# HB-UNI-Sen-RFID-RC_V1_0.net
KiCad netlist of a schematic drawn in EAGLE
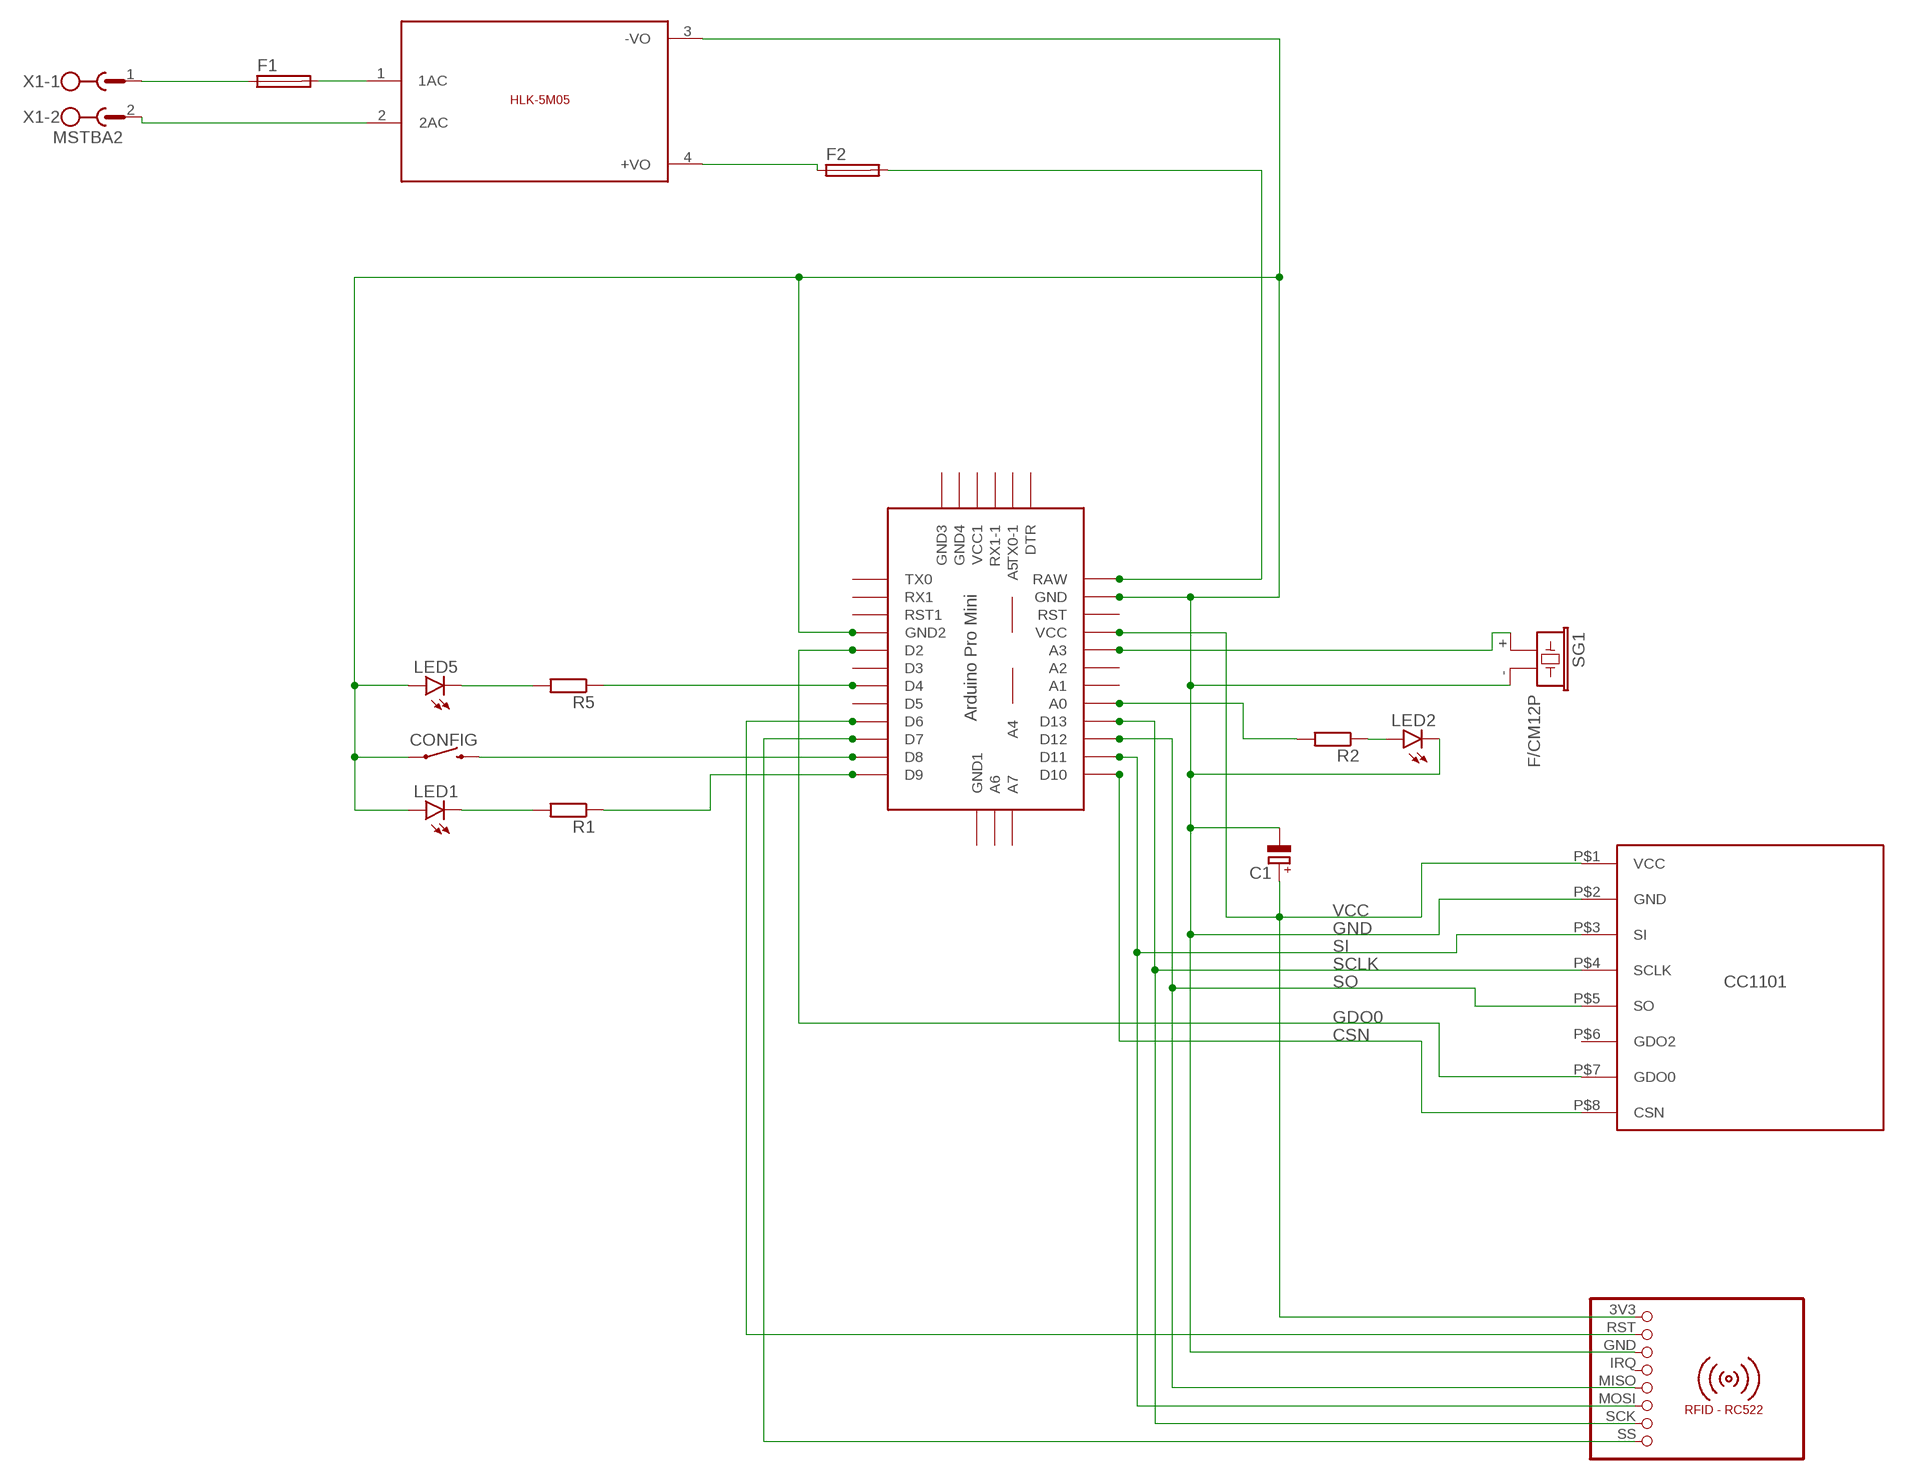
[diagram p0: schematic, sheet 1]

(export (version "E")
  (design (tool "Eeschema 10.0.6"))
  (components
    (comp (ref "C1")
      (value "CPOL-EUE2.5-5")
      (footprint "eagle-import:E2,5-5")
      (libsource (lib "eagle-import") (part "CPOL-EUE2.5-5"))
    )
    (comp (ref "CONFIG")
      (value "MOMENTARY-SWITCH-SPST-PTH-6.0MM-KIT")
      (footprint "eagle-import:TACTILE_SWITCH_PTH_6.0MM_KIT")
      (libsource (lib "eagle-import") (part "MOMENTARY-SWITCH-SPST-PTH-6.0MM-KIT"))
    )
    (comp (ref "F1")
      (value "SH22,5A")
      (footprint "eagle-import:SH22,5A")
      (fields (field (name "MPN") "0031.7701.11"))
      (libsource (lib "eagle-import") (part "SH22,5A"))
    )
    (comp (ref "F2")
      (value "SH22,5A")
      (footprint "eagle-import:SH22,5A")
      (fields (field (name "MPN") "0031.7701.11"))
      (libsource (lib "eagle-import") (part "SH22,5A"))
    )
    (comp (ref "LED1")
      (value "LED3MM")
      (footprint "eagle-import:LED3MM")
      (libsource (lib "eagle-import") (part "LED3MM"))
    )
    (comp (ref "LED2")
      (value "LED3MM")
      (footprint "eagle-import:LED3MM")
      (libsource (lib "eagle-import") (part "LED3MM"))
    )
    (comp (ref "LED5")
      (value "LED3MM")
      (footprint "eagle-import:LED3MM")
      (libsource (lib "eagle-import") (part "LED3MM"))
    )
    (comp (ref "M1")
      (value "RFID-RC522")
      (footprint "eagle-import:RFID-RC522")
      (libsource (lib "eagle-import") (part "RFID-RC522"))
    )
    (comp (ref "R1")
      (value "R-EU_0309/10")
      (footprint "eagle-import:0309_10")
      (libsource (lib "eagle-import") (part "R-EU_0309/10"))
    )
    (comp (ref "R2")
      (value "R-EU_0309/10")
      (footprint "eagle-import:0309_10")
      (libsource (lib "eagle-import") (part "R-EU_0309/10"))
    )
    (comp (ref "R5")
      (value "R-EU_0309/10")
      (footprint "eagle-import:0309_10")
      (libsource (lib "eagle-import") (part "R-EU_0309/10"))
    )
    (comp (ref "SG1")
      (value "F/CM12P")
      (footprint "eagle-import:F_CM12P")
      (libsource (lib "eagle-import") (part "F/CM12P"))
    )
    (comp (ref "U$1")
      (value "CC1101")
      (footprint "eagle-import:CC1101")
      (libsource (lib "eagle-import") (part "CC1101"))
    )
    (comp (ref "U$2")
      (value "ABK-PRO-MINI")
      (footprint "eagle-import:ABK-PRO-MINI")
      (libsource (lib "eagle-import") (part "ABK-PRO-MINI"))
    )
    (comp (ref "U$3")
      (value "5VDC/5W")
      (footprint "eagle-import:HLK-5M05")
      (libsource (lib "eagle-import") (part "HLK-5M05"))
    )
    (comp (ref "X1")
      (value "MSTBA2")
      (footprint "eagle-import:MSTBA2")
      (fields (field (name "MF") "FARNELL") (field (name "MPN") "1757242"))
      (libsource (lib "eagle-import") (part "MSTBA2"))
    )
  )
  (nets
    (net (code "1") (name "/CSN") (class "Default")
      (node (ref "U$1") (pin "P$8") (pinfunction "CSN_P$8") (pintype "bidirectional"))
      (node (ref "U$2") (pin "D10") (pinfunction "D10_D10") (pintype "bidirectional"))
    )
    (net (code "2") (name "/GDO0") (class "Default")
      (node (ref "U$1") (pin "P$7") (pinfunction "GDO0_P$7") (pintype "bidirectional"))
      (node (ref "U$2") (pin "D2") (pinfunction "D2_D2") (pintype "bidirectional"))
    )
    (net (code "3") (name "/GND") (class "Default")
      (node (ref "C1") (pin "-") (pinfunction "-_-") (pintype "passive"))
      (node (ref "CONFIG") (pin "1") (pinfunction "1_1") (pintype "passive"))
      (node (ref "LED1") (pin "A") (pinfunction "A_A") (pintype "passive"))
      (node (ref "LED2") (pin "K") (pinfunction "C_K") (pintype "passive"))
      (node (ref "LED5") (pin "A") (pinfunction "A_A") (pintype "passive"))
      (node (ref "M1") (pin "GND") (pinfunction "3_GND") (pintype "passive"))
      (node (ref "SG1") (pin "-") (pinfunction "2_-") (pintype "passive"))
      (node (ref "U$1") (pin "P$2") (pinfunction "GND_P$2") (pintype "bidirectional"))
      (node (ref "U$2") (pin "GND") (pinfunction "GND_GND") (pintype "bidirectional"))
      (node (ref "U$2") (pin "GND1") (pinfunction "GND2_GND1") (pintype "bidirectional"))
      (node (ref "U$3") (pin "3") (pinfunction "-VO_3") (pintype "bidirectional"))
    )
    (net (code "4") (name "/SCLK") (class "Default")
      (node (ref "M1") (pin "SCK") (pinfunction "7_SCK") (pintype "passive"))
      (node (ref "U$1") (pin "P$4") (pinfunction "SCLK_P$4") (pintype "bidirectional"))
      (node (ref "U$2") (pin "D13") (pinfunction "D13_D13") (pintype "bidirectional"))
    )
    (net (code "5") (name "/SI") (class "Default")
      (node (ref "M1") (pin "MOSI") (pinfunction "6_MOSI") (pintype "passive"))
      (node (ref "U$1") (pin "P$3") (pinfunction "SI_P$3") (pintype "bidirectional"))
      (node (ref "U$2") (pin "D11") (pinfunction "D11_D11") (pintype "bidirectional"))
    )
    (net (code "6") (name "/SO") (class "Default")
      (node (ref "M1") (pin "MISO") (pinfunction "5_MISO") (pintype "passive"))
      (node (ref "U$1") (pin "P$5") (pinfunction "SO_P$5") (pintype "bidirectional"))
      (node (ref "U$2") (pin "D12") (pinfunction "D12_D12") (pintype "bidirectional"))
    )
    (net (code "7") (name "/VCC") (class "Default")
      (node (ref "C1") (pin "+") (pinfunction "+_+") (pintype "passive"))
      (node (ref "M1") (pin "3V3") (pinfunction "1_3V3") (pintype "passive"))
      (node (ref "U$1") (pin "P$1") (pinfunction "VCC_P$1") (pintype "bidirectional"))
      (node (ref "U$2") (pin "VCC") (pinfunction "VCC_VCC") (pintype "bidirectional"))
    )
    (net (code "8") (name "Net-(CONFIG-2)") (class "Default")
      (node (ref "CONFIG") (pin "3") (pinfunction "2_3") (pintype "passive"))
      (node (ref "U$2") (pin "D8") (pinfunction "D8_D8") (pintype "bidirectional"))
    )
    (net (code "9") (name "Net-(F1-Pad1)") (class "Default")
      (node (ref "F1") (pin "1") (pinfunction "1_1") (pintype "passive"))
      (node (ref "X1") (pin "1") (pinfunction "1_1") (pintype "passive"))
    )
    (net (code "10") (name "Net-(F2-Pad2)") (class "Default")
      (node (ref "F2") (pin "2") (pinfunction "2_2") (pintype "passive"))
      (node (ref "U$2") (pin "RAW") (pinfunction "RAW_RAW") (pintype "bidirectional"))
    )
    (net (code "11") (name "Net-(LED1-C)") (class "Default")
      (node (ref "LED1") (pin "K") (pinfunction "C_K") (pintype "passive"))
      (node (ref "R1") (pin "2") (pinfunction "2_2") (pintype "passive"))
    )
    (net (code "12") (name "Net-(LED2-PadA)") (class "Default")
      (node (ref "LED2") (pin "A") (pinfunction "A_A") (pintype "passive"))
      (node (ref "R2") (pin "1") (pinfunction "1_1") (pintype "passive"))
    )
    (net (code "13") (name "Net-(LED5-C)") (class "Default")
      (node (ref "LED5") (pin "K") (pinfunction "C_K") (pintype "passive"))
      (node (ref "R5") (pin "2") (pinfunction "2_2") (pintype "passive"))
    )
    (net (code "14") (name "Net-(M1-2)") (class "Default")
      (node (ref "M1") (pin "RST") (pinfunction "2_RST") (pintype "passive"))
      (node (ref "U$2") (pin "D6") (pinfunction "D6_D6") (pintype "bidirectional"))
    )
    (net (code "15") (name "Net-(M1-8)") (class "Default")
      (node (ref "M1") (pin "SS") (pinfunction "8_SS") (pintype "passive"))
      (node (ref "U$2") (pin "D7") (pinfunction "D7_D7") (pintype "bidirectional"))
    )
    (net (code "16") (name "Net-(R1-Pad1)") (class "Default")
      (node (ref "R1") (pin "1") (pinfunction "1_1") (pintype "passive"))
      (node (ref "U$2") (pin "D9") (pinfunction "D9_D9") (pintype "bidirectional"))
    )
    (net (code "17") (name "Net-(R2-Pad2)") (class "Default")
      (node (ref "R2") (pin "2") (pinfunction "2_2") (pintype "passive"))
      (node (ref "U$2") (pin "A0") (pinfunction "A0_A0") (pintype "bidirectional"))
    )
    (net (code "18") (name "Net-(R5-Pad1)") (class "Default")
      (node (ref "R5") (pin "1") (pinfunction "1_1") (pintype "passive"))
      (node (ref "U$2") (pin "D4") (pinfunction "D4_D4") (pintype "bidirectional"))
    )
    (net (code "19") (name "Net-(SG1-1)") (class "Default")
      (node (ref "SG1") (pin "+") (pinfunction "1_+") (pintype "passive"))
      (node (ref "U$2") (pin "A3") (pinfunction "A3_A3") (pintype "bidirectional"))
    )
    (net (code "20") (name "Net-(U$3-+VO)") (class "Default")
      (node (ref "F2") (pin "1") (pinfunction "1_1") (pintype "passive"))
      (node (ref "U$3") (pin "4") (pinfunction "+VO_4") (pintype "bidirectional"))
    )
    (net (code "21") (name "Net-(U$3-1AC)") (class "Default")
      (node (ref "F1") (pin "2") (pinfunction "2_2") (pintype "passive"))
      (node (ref "U$3") (pin "1") (pinfunction "1AC_1") (pintype "bidirectional"))
    )
    (net (code "22") (name "Net-(U$3-2AC)") (class "Default")
      (node (ref "U$3") (pin "2") (pinfunction "2AC_2") (pintype "bidirectional"))
      (node (ref "X1") (pin "2") (pinfunction "1_2") (pintype "passive"))
    )
    (net (code "23") (name "unconnected-(M1-4-PadIRQ)") (class "Default")
      (node (ref "M1") (pin "IRQ") (pinfunction "4_IRQ") (pintype "passive"))
    )
    (net (code "24") (name "unconnected-(U$1-GDO2-PadP$6)") (class "Default")
      (node (ref "U$1") (pin "P$6") (pinfunction "GDO2_P$6") (pintype "bidirectional"))
    )
    (net (code "25") (name "unconnected-(U$2-GND1-PadGND4)") (class "Default")
      (node (ref "U$2") (pin "GND4") (pinfunction "GND1_GND4") (pintype "bidirectional"))
    )
    (net (code "26") (name "unconnected-(U$2-GND3-PadGND2)") (class "Default")
      (node (ref "U$2") (pin "GND2") (pinfunction "GND3_GND2") (pintype "bidirectional"))
    )
    (net (code "27") (name "unconnected-(U$2-GND4-PadGND3)") (class "Default")
      (node (ref "U$2") (pin "GND3") (pinfunction "GND4_GND3") (pintype "bidirectional"))
    )
    (net (code "28") (name "unconnected-(U$2-PadA1)") (class "Default")
      (node (ref "U$2") (pin "A1") (pinfunction "A1_A1") (pintype "bidirectional"))
    )
    (net (code "29") (name "unconnected-(U$2-PadA2)") (class "Default")
      (node (ref "U$2") (pin "A2") (pinfunction "A2_A2") (pintype "bidirectional"))
    )
    (net (code "30") (name "unconnected-(U$2-PadA4)") (class "Default")
      (node (ref "U$2") (pin "A4") (pinfunction "A4_A4") (pintype "bidirectional"))
    )
    (net (code "31") (name "unconnected-(U$2-PadA5)") (class "Default")
      (node (ref "U$2") (pin "A5") (pinfunction "A5_A5") (pintype "bidirectional"))
    )
    (net (code "32") (name "unconnected-(U$2-PadA6)") (class "Default")
      (node (ref "U$2") (pin "A6") (pinfunction "A6_A6") (pintype "bidirectional"))
    )
    (net (code "33") (name "unconnected-(U$2-PadA7)") (class "Default")
      (node (ref "U$2") (pin "A7") (pinfunction "A7_A7") (pintype "bidirectional"))
    )
    (net (code "34") (name "unconnected-(U$2-PadD3)") (class "Default")
      (node (ref "U$2") (pin "D3") (pinfunction "D3_D3") (pintype "bidirectional"))
    )
    (net (code "35") (name "unconnected-(U$2-PadD5)") (class "Default")
      (node (ref "U$2") (pin "D5") (pinfunction "D5_D5") (pintype "bidirectional"))
    )
    (net (code "36") (name "unconnected-(U$2-PadDTR)") (class "Default")
      (node (ref "U$2") (pin "DTR") (pinfunction "DTR_DTR") (pintype "bidirectional"))
    )
    (net (code "37") (name "unconnected-(U$2-PadRST)") (class "Default")
      (node (ref "U$2") (pin "RST") (pinfunction "RST_RST") (pintype "bidirectional"))
    )
    (net (code "38") (name "unconnected-(U$2-PadRST1)") (class "Default")
      (node (ref "U$2") (pin "RST1") (pinfunction "RST1_RST1") (pintype "bidirectional"))
    )
    (net (code "39") (name "unconnected-(U$2-PadRX1)") (class "Default")
      (node (ref "U$2") (pin "RX1") (pinfunction "RX1_RX1") (pintype "bidirectional"))
    )
    (net (code "40") (name "unconnected-(U$2-PadRX1-1)") (class "Default")
      (node (ref "U$2") (pin "RX1-1") (pinfunction "RX1-1_RX1-1") (pintype "bidirectional"))
    )
    (net (code "41") (name "unconnected-(U$2-PadTX0)") (class "Default")
      (node (ref "U$2") (pin "TX0") (pinfunction "TX0_TX0") (pintype "bidirectional"))
    )
    (net (code "42") (name "unconnected-(U$2-PadTX0-1)") (class "Default")
      (node (ref "U$2") (pin "TX0-1") (pinfunction "TX0-1_TX0-1") (pintype "bidirectional"))
    )
    (net (code "43") (name "unconnected-(U$2-PadVCC1)") (class "Default")
      (node (ref "U$2") (pin "VCC1") (pinfunction "VCC1_VCC1") (pintype "bidirectional"))
    )
  )
)
